# Switches.net
KiCad netlist of a schematic drawn in Altium Designer
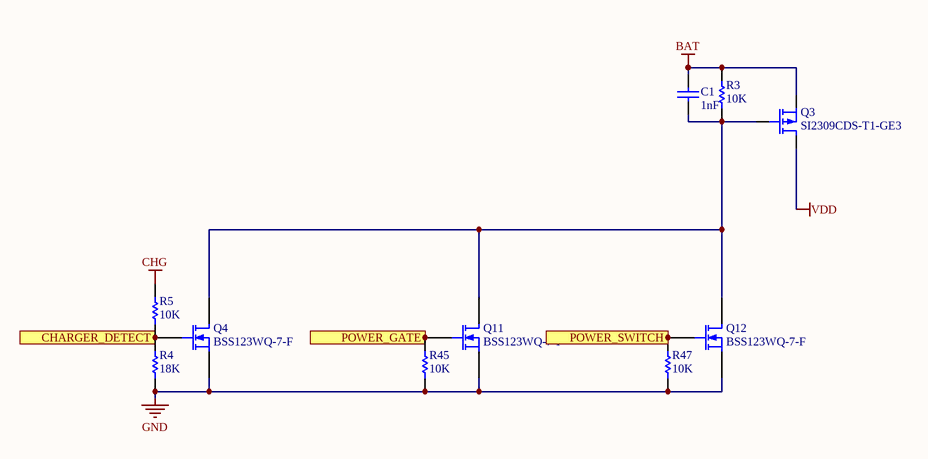
[diagram p0: Switches.SchDoc]

(export (version "E")
  (design (tool "Eeschema 10.0.6"))
  (components
    (comp (ref "C1")
      (value "1nF")
      (footprint "C0603[1608X92]")
      (description "1nF 50V 5% 0603 (1608 Metric)")
      (fields (field (name "PARTNUMBER") "GRM1885C1H102JA01D") (field (name "MANUFACTURER") "Murata"))
      (libsource (lib "Capacitors") (part "CAP_1nF_50V_0603_5%"))
    )
    (comp (ref "Q3")
      (value "SI2309CDS-T1-GE3")
      (footprint "SOT23-3")
      (description "P-Channel MOSFET")
      (fields (field (name "MANUFACTURER") "Vishay"))
      (libsource (lib "MOSFETs") (part "SI2309CDS-T1-GE3"))
    )
    (comp (ref "Q4")
      (value "BSS123WQ-7-F")
      (footprint "SOT323-3")
      (description "N-Channel MOSFET")
      (fields (field (name "MANUFACTURER") "Diodes Incorporated"))
      (libsource (lib "MOSFETs") (part "BSS123WQ-7-F"))
    )
    (comp (ref "Q11")
      (value "BSS123WQ-7-F")
      (footprint "SOT323-3")
      (description "N-Channel MOSFET")
      (fields (field (name "MANUFACTURER") "Diodes Incorporated"))
      (libsource (lib "MOSFETs") (part "BSS123WQ-7-F"))
    )
    (comp (ref "Q12")
      (value "BSS123WQ-7-F")
      (footprint "SOT323-3")
      (description "N-Channel MOSFET")
      (fields (field (name "MANUFACTURER") "Diodes Incorporated"))
      (libsource (lib "MOSFETs") (part "BSS123WQ-7-F"))
    )
    (comp (ref "R3")
      (value "10K")
      (footprint "R0603[1608]")
      (description "10K 0.25W 1% 0603 (1005 Metric)")
      (fields (field (name "POWER") "0.25W") (field (name "TOLERANCE") "1%"))
      (libsource (lib "Resistors") (part "RES_10K_0603_1%"))
    )
    (comp (ref "R4")
      (value "18K")
      (footprint "R0603[1608]")
      (description "18K 0.25W 1% 0603 (1005 Metric)")
      (fields (field (name "TOLERANCE") "1%") (field (name "POWER") "0.25W"))
      (libsource (lib "Resistors") (part "RES_18K_0603_1%"))
    )
    (comp (ref "R5")
      (value "10K")
      (footprint "R0603[1608]")
      (description "10K 0.25W 1% 0603 (1005 Metric)")
      (fields (field (name "MANUFACTURER") "Vishay / Dale") (field (name "PARTNUMBER") "CRCW060310K0FKEAHP"))
      (libsource (lib "Resistors") (part "RES_10K_0603_1%"))
    )
    (comp (ref "R45")
      (value "10K")
      (footprint "R0603[1608]")
      (description "10K 0.25W 1% 0603 (1005 Metric)")
      (fields (field (name "MANUFACTURER") "Vishay / Dale") (field (name "PARTNUMBER") "CRCW060310K0FKEAHP"))
      (libsource (lib "Resistors") (part "RES_10K_0603_1%"))
    )
    (comp (ref "R47")
      (value "10K")
      (footprint "R0603[1608]")
      (description "10K 0.25W 1% 0603 (1005 Metric)")
      (fields (field (name "POWER") "0.25W") (field (name "TOLERANCE") "1%"))
      (libsource (lib "Resistors") (part "RES_10K_0603_1%"))
    )
  )
  (nets
    (net (code "1") (name "/CHARGER_DETECT") (class "Default")
      (node (ref "Q4") (pin "1") (pinfunction "G_1") (pintype "passive"))
      (node (ref "R4") (pin "2") (pinfunction "2_2") (pintype "passive"))
      (node (ref "R5") (pin "1") (pinfunction "1_1") (pintype "passive"))
    )
    (net (code "2") (name "/POWER_GATE") (class "Default")
      (node (ref "Q11") (pin "1") (pinfunction "G_1") (pintype "passive"))
      (node (ref "R45") (pin "2") (pinfunction "2_2") (pintype "passive"))
    )
    (net (code "3") (name "/POWER_SWITCH") (class "Default")
      (node (ref "Q12") (pin "1") (pinfunction "G_1") (pintype "passive"))
      (node (ref "R47") (pin "2") (pinfunction "2_2") (pintype "passive"))
    )
    (net (code "4") (name "BAT") (class "Default")
      (node (ref "C1") (pin "2") (pinfunction "2_2") (pintype "passive"))
      (node (ref "Q3") (pin "3") (pinfunction "S_3") (pintype "passive"))
      (node (ref "R3") (pin "2") (pinfunction "2_2") (pintype "passive"))
    )
    (net (code "5") (name "CHG") (class "Default")
      (node (ref "R5") (pin "2") (pinfunction "2_2") (pintype "passive"))
    )
    (net (code "6") (name "GND") (class "Default")
      (node (ref "Q11") (pin "2") (pinfunction "S_2") (pintype "passive"))
      (node (ref "Q12") (pin "2") (pinfunction "S_2") (pintype "passive"))
      (node (ref "Q4") (pin "2") (pinfunction "S_2") (pintype "passive"))
      (node (ref "R4") (pin "1") (pinfunction "1_1") (pintype "passive"))
      (node (ref "R45") (pin "1") (pinfunction "1_1") (pintype "passive"))
      (node (ref "R47") (pin "1") (pinfunction "1_1") (pintype "passive"))
    )
    (net (code "7") (name "Net-(Q11-D)") (class "Default")
      (node (ref "C1") (pin "1") (pinfunction "1_1") (pintype "passive"))
      (node (ref "Q11") (pin "3") (pinfunction "D_3") (pintype "passive"))
      (node (ref "Q12") (pin "3") (pinfunction "D_3") (pintype "passive"))
      (node (ref "Q3") (pin "1") (pinfunction "G_1") (pintype "passive"))
      (node (ref "Q4") (pin "3") (pinfunction "D_3") (pintype "passive"))
      (node (ref "R3") (pin "1") (pinfunction "1_1") (pintype "passive"))
    )
    (net (code "8") (name "VDD") (class "Default")
      (node (ref "Q3") (pin "2") (pinfunction "D_2") (pintype "passive"))
    )
  )
)
